# design.net
KiCad netlist of a schematic drawn in EasyEDA Pro
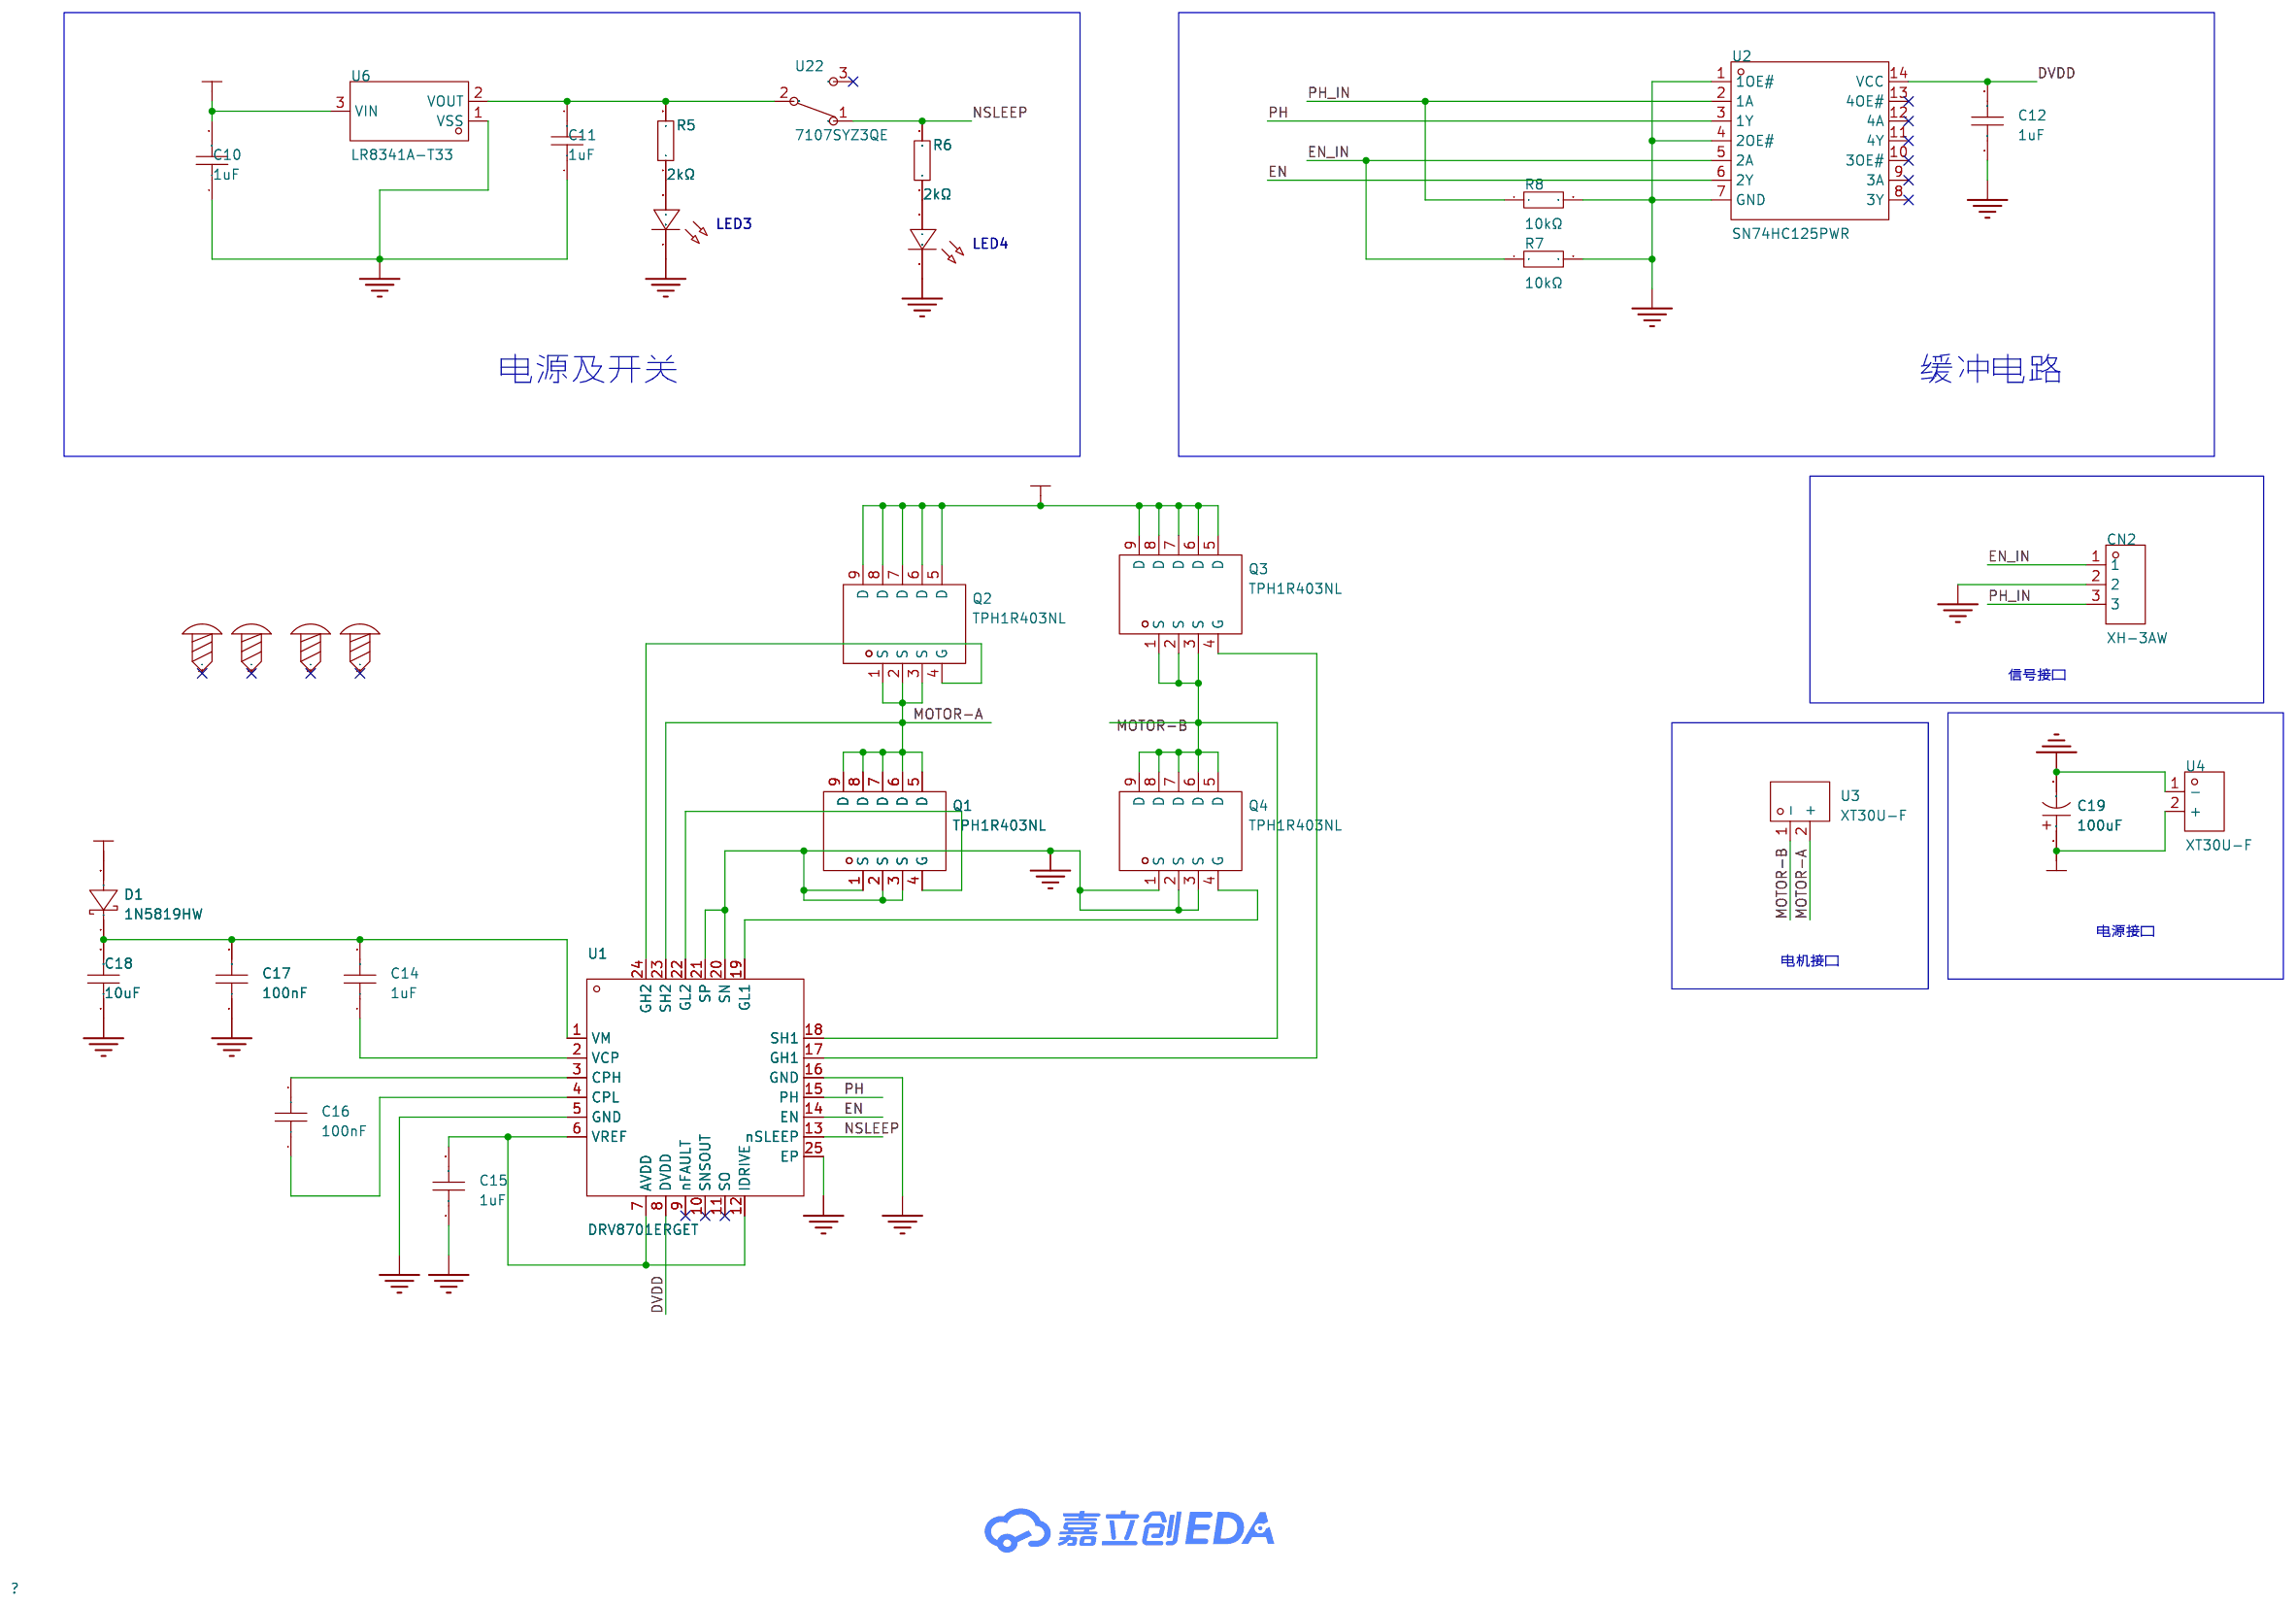
[diagram p0: schematic sheet]

(export (version "E")
  (design (tool "Eeschema 10.0.6"))
  (components
    (comp (ref "C10")
      (value "1uF")
      (footprint "easyedapro:C0603")
      (description "容值:1uF;精度:±10%;额定电压:50V;材质(温度系数):X5R;")
      (fields
        (field (name "Manufacturer Part") "CGA0603X5R105K500JT")
        (field (name "Manufacturer") "HRE(芯声)")
      )
      (libsource (lib "easyedapro") (part "CGA0603X5R105K500JT"))
    )
    (comp (ref "C11")
      (value "1uF")
      (footprint "easyedapro:C0603")
      (description "容值:1uF;精度:±10%;额定电压:50V;材质(温度系数):X5R;")
      (fields
        (field (name "Manufacturer Part") "CGA0603X5R105K500JT")
        (field (name "Manufacturer") "HRE(芯声)")
      )
      (libsource (lib "easyedapro") (part "CGA0603X5R105K500JT"))
    )
    (comp (ref "C12")
      (value "1uF")
      (footprint "easyedapro:C0603")
      (description "容值:1uF;精度:±10%;额定电压:50V;材质(温度系数):X5R;")
      (fields
        (field (name "Manufacturer Part") "CGA0603X5R105K500JT")
        (field (name "Manufacturer") "HRE(芯声)")
      )
      (libsource (lib "easyedapro") (part "CGA0603X5R105K500JT"))
    )
    (comp (ref "C14")
      (value "1uF")
      (footprint "easyedapro:C0603")
      (description "容值:1uF;精度:±10%;额定电压:50V;材质(温度系数):X5R;")
      (fields
        (field (name "Manufacturer Part") "CGA0603X5R105K500JT")
        (field (name "Manufacturer") "HRE(芯声)")
      )
      (libsource (lib "easyedapro") (part "CGA0603X5R105K500JT"))
    )
    (comp (ref "C15")
      (value "1uF")
      (footprint "easyedapro:C0603")
      (description "容值:1uF;精度:±10%;额定电压:50V;材质(温度系数):X5R;")
      (fields
        (field (name "Manufacturer Part") "CGA0603X5R105K500JT")
        (field (name "Manufacturer") "HRE(芯声)")
      )
      (libsource (lib "easyedapro") (part "CGA0603X5R105K500JT"))
    )
    (comp (ref "C16")
      (value "100nF")
      (footprint "easyedapro:C0603")
      (description "容值:100nF;精度:±10%;额定电压:50V;材质(温度系数):X7R;")
      (fields
        (field (name "Manufacturer Part") "CGA0603X7R104K500JT")
        (field (name "Manufacturer") "HRE(芯声)")
      )
      (libsource (lib "easyedapro") (part "CGA0603X7R104K500JT"))
    )
    (comp (ref "C17")
      (value "100nF")
      (footprint "easyedapro:C0603")
      (description "容值:100nF;精度:±10%;额定电压:50V;材质(温度系数):X7R;")
      (fields
        (field (name "Manufacturer Part") "CGA0603X7R104K500JT")
        (field (name "Manufacturer") "HRE(芯声)")
      )
      (libsource (lib "easyedapro") (part "CGA0603X7R104K500JT"))
    )
    (comp (ref "C18")
      (value "10uF")
      (footprint "easyedapro:C0603")
      (description "容值:10uF;精度:±20%;额定电压:16V;材质(温度系数):X5R;")
      (fields
        (field (name "Manufacturer Part") "HGC0603R5106M160NTHJ")
        (field (name "Manufacturer") "Chinocera(华瓷)")
      )
      (libsource (lib "easyedapro") (part "HGC0603R5106M160NTHJ"))
    )
    (comp (ref "C19")
      (value "100uF")
      (footprint "easyedapro:CAP-TH_BD6.3-P2.50-D0.6-FD-1")
      (description "容值:100uF;精度:±20%;额定电压:50V;纹波电流:2.98A@100Hz;等效串联电阻(ESR):25mΩ@100kHz;类型:-;")
      (fields (field (name "Manufacturer Part") "PA50V100M6x12") (field (name "Manufacturer") "捷而瑞"))
      (libsource (lib "easyedapro") (part "PA50V100M6X12"))
    )
    (comp (ref "CN2")
      (value "XH-3AW")
      (footprint "easyedapro:CONN-TH_3P-P2.54_HCTL_XH-3AW")
      (fields (field (name "Manufacturer") "HCTL(华灿天禄)"))
      (libsource (lib "easyedapro") (part "XH-3AW_C2908612"))
    )
    (comp (ref "D1")
      (value "1N5819HW")
      (footprint "easyedapro:SOD-123_L2.7-W1.6-LS3.7-RD-1")
      (description "二极管配置:-;正向压降(Vf):900mV@3A;直流反向耐压(Vr):40V;平均整流电流(Io):1A;")
      (fields (field (name "Manufacturer") "TECH PUBLIC(台舟)"))
      (libsource (lib "easyedapro") (part "1N5819HW"))
    )
    (comp (ref "LED3")
      (value "~")
      (footprint "easyedapro:LED_0805")
      (libsource (lib "easyedapro") (part "LED_G"))
    )
    (comp (ref "LED4")
      (value "~")
      (footprint "easyedapro:LED_0805")
      (libsource (lib "easyedapro") (part "LED_G"))
    )
    (comp (ref "Q1")
      (value "TPH1R403NL")
      (footprint "easyedapro:DSOP-8_L5.0-W5.0-P1.27-LS6.0-BL-EP")
      (fields (field (name "Manufacturer") "TOSHIBA(东芝)"))
      (libsource (lib "easyedapro") (part "TPH1R403NL"))
    )
    (comp (ref "Q2")
      (value "TPH1R403NL")
      (footprint "easyedapro:DSOP-8_L5.0-W5.0-P1.27-LS6.0-BL-EP")
      (fields (field (name "Manufacturer") "TOSHIBA(东芝)"))
      (libsource (lib "easyedapro") (part "TPH1R403NL"))
    )
    (comp (ref "Q3")
      (value "TPH1R403NL")
      (footprint "easyedapro:DSOP-8_L5.0-W5.0-P1.27-LS6.0-BL-EP")
      (fields (field (name "Manufacturer") "TOSHIBA(东芝)"))
      (libsource (lib "easyedapro") (part "TPH1R403NL"))
    )
    (comp (ref "Q4")
      (value "TPH1R403NL")
      (footprint "easyedapro:DSOP-8_L5.0-W5.0-P1.27-LS6.0-BL-EP")
      (fields (field (name "Manufacturer") "TOSHIBA(东芝)"))
      (libsource (lib "easyedapro") (part "TPH1R403NL"))
    )
    (comp (ref "R5")
      (value "2kΩ")
      (footprint "easyedapro:R0603")
      (description "电阻类型:厚膜电阻;阻值:2kΩ;精度:±1%;功率:100mW;最大工作电压:75V;温度系数:±100ppm/°C;")
      (fields
        (field (name "Manufacturer Part") "0603WAF2001T5E")
        (field (name "Manufacturer") "UNI-ROYAL(厚声)")
      )
      (libsource (lib "easyedapro") (part "0603WAF2001T5E"))
    )
    (comp (ref "R6")
      (value "2kΩ")
      (footprint "easyedapro:R0603")
      (description "电阻类型:厚膜电阻;阻值:2kΩ;精度:±1%;功率:100mW;最大工作电压:75V;温度系数:±100ppm/°C;")
      (fields
        (field (name "Manufacturer Part") "0603WAF2001T5E")
        (field (name "Manufacturer") "UNI-ROYAL(厚声)")
      )
      (libsource (lib "easyedapro") (part "0603WAF2001T5E"))
    )
    (comp (ref "R7")
      (value "10kΩ")
      (footprint "easyedapro:R0603")
      (description "电阻类型:厚膜电阻;阻值:10kΩ;精度:±1%;功率:100mW;最大工作电压:75V;温度系数:±100ppm/°C;")
      (fields
        (field (name "Manufacturer Part") "0603WAF1002T5E")
        (field (name "Manufacturer") "UNI-ROYAL(厚声)")
      )
      (libsource (lib "easyedapro") (part "0603WAF1002T5E"))
    )
    (comp (ref "R8")
      (value "10kΩ")
      (footprint "easyedapro:R0603")
      (description "电阻类型:厚膜电阻;阻值:10kΩ;精度:±1%;功率:100mW;最大工作电压:75V;温度系数:±100ppm/°C;")
      (fields
        (field (name "Manufacturer Part") "0603WAF1002T5E")
        (field (name "Manufacturer") "UNI-ROYAL(厚声)")
      )
      (libsource (lib "easyedapro") (part "0603WAF1002T5E"))
    )
    (comp (ref "SCREW1")
      (value "~")
      (footprint "easyedapro:M3螺丝")
      (libsource (lib "easyedapro") (part "螺丝孔"))
    )
    (comp (ref "SCREW2")
      (value "~")
      (footprint "easyedapro:M3螺丝")
      (libsource (lib "easyedapro") (part "螺丝孔"))
    )
    (comp (ref "SCREW3")
      (value "~")
      (footprint "easyedapro:M3螺丝")
      (libsource (lib "easyedapro") (part "螺丝孔"))
    )
    (comp (ref "SCREW4")
      (value "~")
      (footprint "easyedapro:M3螺丝")
      (libsource (lib "easyedapro") (part "螺丝孔"))
    )
    (comp (ref "U1")
      (value "DRV8701ERGET")
      (footprint "easyedapro:VQFN-24_L4.0-W4.0-P0.50-BL-EP2.5")
      (description "驱动电机类型:有刷直流电机;电源电压:0V~5.5V;输出电流:-;接口:并行;")
      (fields (field (name "Manufacturer") "TI(德州仪器)"))
      (libsource (lib "easyedapro") (part "DRV8701ERGET"))
    )
    (comp (ref "U2")
      (value "SN74HC125PWR")
      (footprint "easyedapro:TSSOP-14_L5.0-W4.4-P0.65-LS6.5-BL")
      (description "输入类型:-;电源电压:2V~6V;元件数:4;每个元件位数:1;灌电流(IOL):7.8mA;拉电流(IOH):7.8mA;")
      (fields (field (name "Manufacturer") "TI(德州仪器)"))
      (libsource (lib "easyedapro") (part "SN74HC125PWR"))
    )
    (comp (ref "U3")
      (value "XT30U-F")
      (footprint "easyedapro:CONN-TH_XT30U-F")
      (description "类别:-;类型1:-;")
      (fields (field (name "Manufacturer") "AMASS(艾迈斯)"))
      (libsource (lib "easyedapro") (part "XT30U-F"))
    )
    (comp (ref "U4")
      (value "XT30U-F")
      (footprint "easyedapro:CONN-TH_XT30U-F")
      (description "类别:-;类型1:-;")
      (fields (field (name "Manufacturer") "AMASS(艾迈斯)"))
      (libsource (lib "easyedapro") (part "XT30U-F"))
    )
    (comp (ref "U6")
      (value "LR8341A-T33")
      (footprint "easyedapro:SOT-23-3L_L2.9-W1.6-P1.90-LS2.8-BL")
      (description "输出类型:固定;最大输入电压:40V;输出电压:3.3V;最大输出电流:100mA;电源纹波抑制比(PSRR):55dB@(1kHz);输出极性:正极;")
      (fields (field (name "Manufacturer") "LR(朗瑞)"))
      (libsource (lib "easyedapro") (part "LR8341A-T33"))
    )
    (comp (ref "U22")
      (value "7107SYZ3QE")
      (footprint "easyedapro:SW-TH_3P-L12.7-W6.8-P4.70")
      (description "电路结构:单刀双掷;额定电压(AC):120V;额定电压(DC):28V;安装方式:直插;")
      (fields (field (name "Manufacturer") "CK"))
      (libsource (lib "easyedapro") (part "7107SYZ3QE"))
    )
  )
  (nets
    (net (code "1") (name "/DVDD") (class "Default")
      (node (ref "C12") (pin "2") (pinfunction "2_2") (pintype "unspecified"))
      (node (ref "U1") (pin "8") (pinfunction "DVDD_8") (pintype "unspecified"))
      (node (ref "U2") (pin "14") (pinfunction "VCC_14") (pintype "input"))
    )
    (net (code "2") (name "/EN") (class "Default")
      (node (ref "U1") (pin "14") (pinfunction "EN_14") (pintype "unspecified"))
      (node (ref "U2") (pin "6") (pinfunction "2Y_6") (pintype "input"))
    )
    (net (code "3") (name "/EN_IN") (class "Default")
      (node (ref "CN2") (pin "1") (pinfunction "1_1") (pintype "unspecified"))
      (node (ref "R7") (pin "1") (pinfunction "1_1") (pintype "input"))
      (node (ref "U2") (pin "5") (pinfunction "2A_5") (pintype "input"))
    )
    (net (code "4") (name "/MOTOR-A") (class "Default")
      (node (ref "Q1") (pin "5") (pinfunction "D_5") (pintype "unspecified"))
      (node (ref "Q1") (pin "6") (pinfunction "D_6") (pintype "unspecified"))
      (node (ref "Q1") (pin "7") (pinfunction "D_7") (pintype "unspecified"))
      (node (ref "Q1") (pin "8") (pinfunction "D_8") (pintype "unspecified"))
      (node (ref "Q1") (pin "9") (pinfunction "D_9") (pintype "unspecified"))
      (node (ref "Q2") (pin "1") (pinfunction "S_1") (pintype "unspecified"))
      (node (ref "Q2") (pin "2") (pinfunction "S_2") (pintype "unspecified"))
      (node (ref "Q2") (pin "3") (pinfunction "S_3") (pintype "unspecified"))
      (node (ref "U1") (pin "23") (pinfunction "SH2_23") (pintype "unspecified"))
      (node (ref "U3") (pin "2") (pinfunction "+_2") (pintype "unspecified"))
    )
    (net (code "5") (name "/MOTOR-B") (class "Default")
      (node (ref "Q3") (pin "1") (pinfunction "S_1") (pintype "unspecified"))
      (node (ref "Q3") (pin "2") (pinfunction "S_2") (pintype "unspecified"))
      (node (ref "Q3") (pin "3") (pinfunction "S_3") (pintype "unspecified"))
      (node (ref "Q4") (pin "5") (pinfunction "D_5") (pintype "unspecified"))
      (node (ref "Q4") (pin "6") (pinfunction "D_6") (pintype "unspecified"))
      (node (ref "Q4") (pin "7") (pinfunction "D_7") (pintype "unspecified"))
      (node (ref "Q4") (pin "8") (pinfunction "D_8") (pintype "unspecified"))
      (node (ref "Q4") (pin "9") (pinfunction "D_9") (pintype "unspecified"))
      (node (ref "U1") (pin "18") (pinfunction "SH1_18") (pintype "unspecified"))
      (node (ref "U3") (pin "1") (pinfunction "-_1") (pintype "unspecified"))
    )
    (net (code "6") (name "/NSLEEP") (class "Default")
      (node (ref "R6") (pin "2") (pinfunction "2_2") (pintype "input"))
      (node (ref "U1") (pin "13") (pinfunction "nSLEEP_13") (pintype "unspecified"))
      (node (ref "U22") (pin "1") (pinfunction "ON_1") (pintype "unspecified"))
    )
    (net (code "7") (name "/PH") (class "Default")
      (node (ref "U1") (pin "15") (pinfunction "PH_15") (pintype "unspecified"))
      (node (ref "U2") (pin "3") (pinfunction "1Y_3") (pintype "input"))
    )
    (net (code "8") (name "/PH_IN") (class "Default")
      (node (ref "CN2") (pin "3") (pinfunction "3_3") (pintype "unspecified"))
      (node (ref "R8") (pin "1") (pinfunction "1_1") (pintype "input"))
      (node (ref "U2") (pin "2") (pinfunction "1A_2") (pintype "input"))
    )
    (net (code "9") (name "GND") (class "Default")
      (node (ref "C10") (pin "1") (pinfunction "1_1") (pintype "unspecified"))
      (node (ref "C11") (pin "1") (pinfunction "1_1") (pintype "unspecified"))
      (node (ref "C12") (pin "1") (pinfunction "1_1") (pintype "unspecified"))
      (node (ref "C15") (pin "1") (pinfunction "1_1") (pintype "unspecified"))
      (node (ref "C17") (pin "1") (pinfunction "1_1") (pintype "unspecified"))
      (node (ref "C18") (pin "1") (pinfunction "1_1") (pintype "unspecified"))
      (node (ref "C19") (pin "2") (pinfunction "2_2") (pintype "input"))
      (node (ref "CN2") (pin "2") (pinfunction "2_2") (pintype "unspecified"))
      (node (ref "LED3") (pin "1") (pinfunction "C_1") (pintype "input"))
      (node (ref "LED4") (pin "1") (pinfunction "C_1") (pintype "input"))
      (node (ref "Q1") (pin "1") (pinfunction "S_1") (pintype "unspecified"))
      (node (ref "Q1") (pin "2") (pinfunction "S_2") (pintype "unspecified"))
      (node (ref "Q1") (pin "3") (pinfunction "S_3") (pintype "unspecified"))
      (node (ref "Q4") (pin "1") (pinfunction "S_1") (pintype "unspecified"))
      (node (ref "Q4") (pin "2") (pinfunction "S_2") (pintype "unspecified"))
      (node (ref "Q4") (pin "3") (pinfunction "S_3") (pintype "unspecified"))
      (node (ref "R7") (pin "2") (pinfunction "2_2") (pintype "input"))
      (node (ref "R8") (pin "2") (pinfunction "2_2") (pintype "input"))
      (node (ref "U1") (pin "16") (pinfunction "GND_16") (pintype "unspecified"))
      (node (ref "U1") (pin "20") (pinfunction "SN_20") (pintype "unspecified"))
      (node (ref "U1") (pin "21") (pinfunction "SP_21") (pintype "unspecified"))
      (node (ref "U1") (pin "25") (pinfunction "EP_25") (pintype "unspecified"))
      (node (ref "U1") (pin "5") (pinfunction "GND_5") (pintype "unspecified"))
      (node (ref "U2") (pin "1") (pinfunction "1OE#_1") (pintype "input"))
      (node (ref "U2") (pin "4") (pinfunction "2OE#_4") (pintype "input"))
      (node (ref "U2") (pin "7") (pinfunction "GND_7") (pintype "input"))
      (node (ref "U4") (pin "1") (pinfunction "-_1") (pintype "unspecified"))
      (node (ref "U6") (pin "1") (pinfunction "VSS_1") (pintype "unspecified"))
    )
    (net (code "10") (name "Net-(D1-K)") (class "Default")
      (node (ref "C14") (pin "2") (pinfunction "2_2") (pintype "unspecified"))
      (node (ref "C17") (pin "2") (pinfunction "2_2") (pintype "unspecified"))
      (node (ref "C18") (pin "2") (pinfunction "2_2") (pintype "unspecified"))
      (node (ref "D1") (pin "1") (pinfunction "K_1") (pintype "input"))
      (node (ref "U1") (pin "1") (pinfunction "VM_1") (pintype "unspecified"))
    )
    (net (code "11") (name "Net-(LED3-A)") (class "Default")
      (node (ref "LED3") (pin "2") (pinfunction "A_2") (pintype "input"))
      (node (ref "R5") (pin "1") (pinfunction "1_1") (pintype "input"))
    )
    (net (code "12") (name "Net-(LED4-A)") (class "Default")
      (node (ref "LED4") (pin "2") (pinfunction "A_2") (pintype "input"))
      (node (ref "R6") (pin "1") (pinfunction "1_1") (pintype "input"))
    )
    (net (code "13") (name "Net-(Q1-G)") (class "Default")
      (node (ref "Q1") (pin "4") (pinfunction "G_4") (pintype "unspecified"))
      (node (ref "U1") (pin "22") (pinfunction "GL2_22") (pintype "unspecified"))
    )
    (net (code "14") (name "Net-(Q2-G)") (class "Default")
      (node (ref "Q2") (pin "4") (pinfunction "G_4") (pintype "unspecified"))
      (node (ref "U1") (pin "24") (pinfunction "GH2_24") (pintype "unspecified"))
    )
    (net (code "15") (name "Net-(Q3-G)") (class "Default")
      (node (ref "Q3") (pin "4") (pinfunction "G_4") (pintype "unspecified"))
      (node (ref "U1") (pin "17") (pinfunction "GH1_17") (pintype "unspecified"))
    )
    (net (code "16") (name "Net-(Q4-G)") (class "Default")
      (node (ref "Q4") (pin "4") (pinfunction "G_4") (pintype "unspecified"))
      (node (ref "U1") (pin "19") (pinfunction "GL1_19") (pintype "unspecified"))
    )
    (net (code "17") (name "Net-(U1-AVDD)") (class "Default")
      (node (ref "C15") (pin "2") (pinfunction "2_2") (pintype "unspecified"))
      (node (ref "U1") (pin "12") (pinfunction "IDRIVE_12") (pintype "unspecified"))
      (node (ref "U1") (pin "6") (pinfunction "VREF_6") (pintype "unspecified"))
      (node (ref "U1") (pin "7") (pinfunction "AVDD_7") (pintype "unspecified"))
    )
    (net (code "18") (name "Net-(U1-CPH)") (class "Default")
      (node (ref "C16") (pin "2") (pinfunction "2_2") (pintype "unspecified"))
      (node (ref "U1") (pin "3") (pinfunction "CPH_3") (pintype "unspecified"))
    )
    (net (code "19") (name "Net-(U1-CPL)") (class "Default")
      (node (ref "C16") (pin "1") (pinfunction "1_1") (pintype "unspecified"))
      (node (ref "U1") (pin "4") (pinfunction "CPL_4") (pintype "unspecified"))
    )
    (net (code "20") (name "Net-(U1-VCP)") (class "Default")
      (node (ref "C14") (pin "1") (pinfunction "1_1") (pintype "unspecified"))
      (node (ref "U1") (pin "2") (pinfunction "VCP_2") (pintype "unspecified"))
    )
    (net (code "21") (name "Net-(U22-COMM)") (class "Default")
      (node (ref "C11") (pin "2") (pinfunction "2_2") (pintype "unspecified"))
      (node (ref "R5") (pin "2") (pinfunction "2_2") (pintype "input"))
      (node (ref "U22") (pin "2") (pinfunction "COMM_2") (pintype "unspecified"))
      (node (ref "U6") (pin "2") (pinfunction "VOUT_2") (pintype "unspecified"))
    )
    (net (code "22") (name "VIN") (class "Default")
      (node (ref "C10") (pin "2") (pinfunction "2_2") (pintype "unspecified"))
      (node (ref "C19") (pin "1") (pinfunction "1_1") (pintype "input"))
      (node (ref "D1") (pin "2") (pinfunction "A_2") (pintype "input"))
      (node (ref "Q2") (pin "5") (pinfunction "D_5") (pintype "unspecified"))
      (node (ref "Q2") (pin "6") (pinfunction "D_6") (pintype "unspecified"))
      (node (ref "Q2") (pin "7") (pinfunction "D_7") (pintype "unspecified"))
      (node (ref "Q2") (pin "8") (pinfunction "D_8") (pintype "unspecified"))
      (node (ref "Q2") (pin "9") (pinfunction "D_9") (pintype "unspecified"))
      (node (ref "Q3") (pin "5") (pinfunction "D_5") (pintype "unspecified"))
      (node (ref "Q3") (pin "6") (pinfunction "D_6") (pintype "unspecified"))
      (node (ref "Q3") (pin "7") (pinfunction "D_7") (pintype "unspecified"))
      (node (ref "Q3") (pin "8") (pinfunction "D_8") (pintype "unspecified"))
      (node (ref "Q3") (pin "9") (pinfunction "D_9") (pintype "unspecified"))
      (node (ref "U4") (pin "2") (pinfunction "+_2") (pintype "unspecified"))
      (node (ref "U6") (pin "3") (pinfunction "VIN_3") (pintype "unspecified"))
    )
    (net (code "23") (name "unconnected-(SCREW1-Pad1)") (class "Default")
      (node (ref "SCREW1") (pin "1") (pinfunction "1_1") (pintype "input+no_connect"))
    )
    (net (code "24") (name "unconnected-(SCREW2-Pad1)") (class "Default")
      (node (ref "SCREW2") (pin "1") (pinfunction "1_1") (pintype "input+no_connect"))
    )
    (net (code "25") (name "unconnected-(SCREW3-Pad1)") (class "Default")
      (node (ref "SCREW3") (pin "1") (pinfunction "1_1") (pintype "input+no_connect"))
    )
    (net (code "26") (name "unconnected-(SCREW4-Pad1)") (class "Default")
      (node (ref "SCREW4") (pin "1") (pinfunction "1_1") (pintype "input+no_connect"))
    )
    (net (code "27") (name "unconnected-(U1-SNSOUT-Pad10)") (class "Default")
      (node (ref "U1") (pin "10") (pinfunction "SNSOUT_10") (pintype "unspecified+no_connect"))
    )
    (net (code "28") (name "unconnected-(U1-SO-Pad11)") (class "Default")
      (node (ref "U1") (pin "11") (pinfunction "SO_11") (pintype "unspecified+no_connect"))
    )
    (net (code "29") (name "unconnected-(U1-nFAULT-Pad9)") (class "Default")
      (node (ref "U1") (pin "9") (pinfunction "nFAULT_9") (pintype "unspecified+no_connect"))
    )
    (net (code "30") (name "unconnected-(U2-3A-Pad9)") (class "Default")
      (node (ref "U2") (pin "9") (pinfunction "3A_9") (pintype "input+no_connect"))
    )
    (net (code "31") (name "unconnected-(U2-3OE#-Pad10)") (class "Default")
      (node (ref "U2") (pin "10") (pinfunction "3OE#_10") (pintype "input+no_connect"))
    )
    (net (code "32") (name "unconnected-(U2-3Y-Pad8)") (class "Default")
      (node (ref "U2") (pin "8") (pinfunction "3Y_8") (pintype "input+no_connect"))
    )
    (net (code "33") (name "unconnected-(U2-4A-Pad12)") (class "Default")
      (node (ref "U2") (pin "12") (pinfunction "4A_12") (pintype "input+no_connect"))
    )
    (net (code "34") (name "unconnected-(U2-4OE#-Pad13)") (class "Default")
      (node (ref "U2") (pin "13") (pinfunction "4OE#_13") (pintype "input+no_connect"))
    )
    (net (code "35") (name "unconnected-(U2-4Y-Pad11)") (class "Default")
      (node (ref "U2") (pin "11") (pinfunction "4Y_11") (pintype "input+no_connect"))
    )
    (net (code "36") (name "unconnected-(U22-NC-Pad3)") (class "Default")
      (node (ref "U22") (pin "3") (pinfunction "NC_3") (pintype "unspecified+no_connect"))
    )
  )
)
